# soundmeter.net
KiCad netlist of a schematic drawn in EAGLE
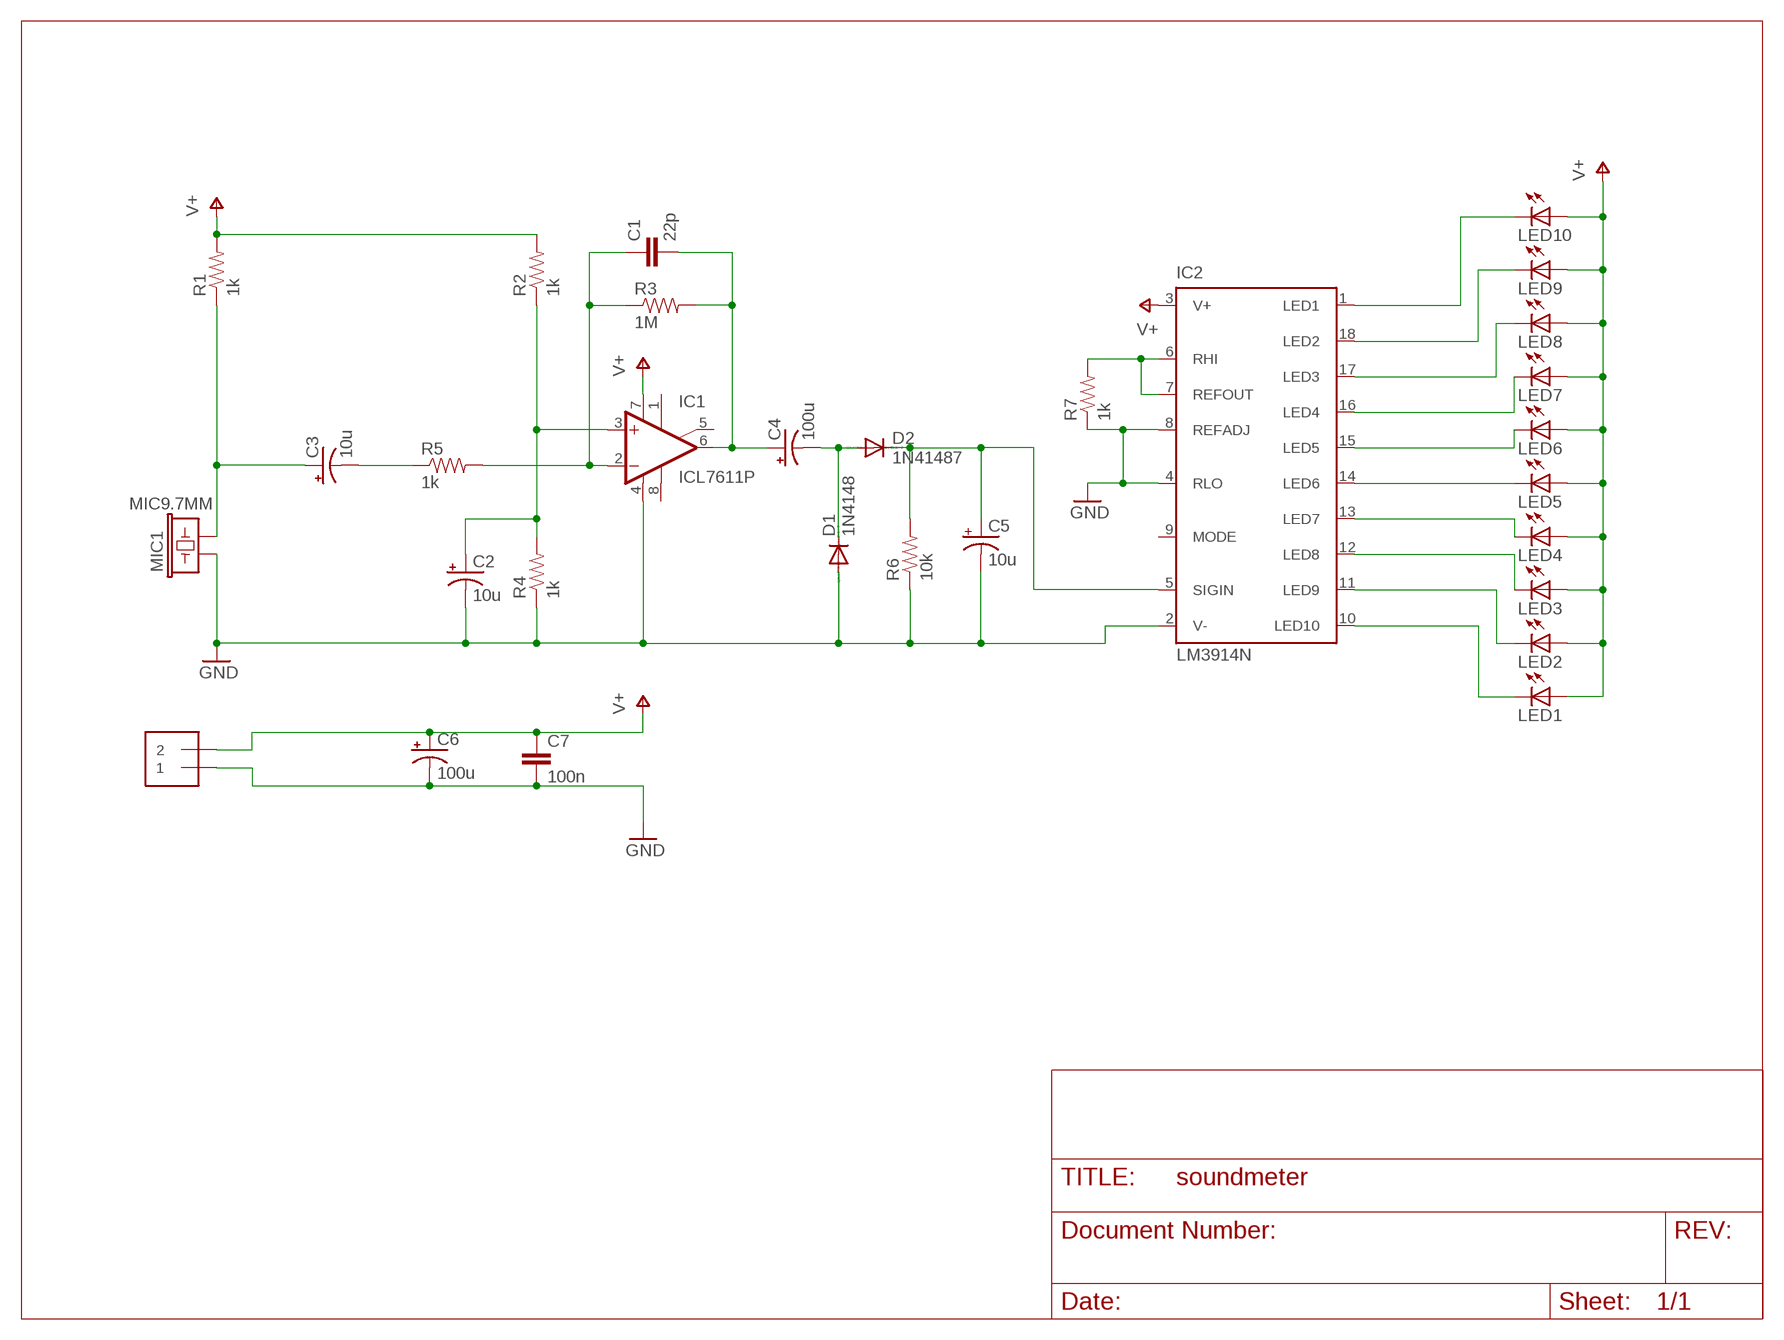
[diagram p0: schematic, sheet 1]

(export (version "E")
  (design (tool "Eeschema 10.0.6"))
  (components
    (comp (ref "C1")
      (value "22p")
      (footprint "eagle-import:CAP-PTH-SMALL")
      (libsource (lib "eagle-import") (part "CAPPTH"))
    )
    (comp (ref "C2")
      (value "10u")
      (footprint "eagle-import:CPOL-RADIAL-10UF-25V")
      (libsource (lib "eagle-import") (part "CAP_POLPTH2"))
    )
    (comp (ref "C3")
      (value "10u")
      (footprint "eagle-import:CPOL-RADIAL-10UF-25V")
      (libsource (lib "eagle-import") (part "CAP_POLPTH2"))
    )
    (comp (ref "C4")
      (value "100u")
      (footprint "eagle-import:CPOL-RADIAL-10UF-25V")
      (libsource (lib "eagle-import") (part "CAP_POLPTH2"))
    )
    (comp (ref "C5")
      (value "10u")
      (footprint "eagle-import:CPOL-RADIAL-10UF-25V")
      (libsource (lib "eagle-import") (part "CAP_POLPTH2"))
    )
    (comp (ref "C6")
      (value "100u")
      (footprint "eagle-import:CPOL-RADIAL-10UF-25V")
      (libsource (lib "eagle-import") (part "CAP_POLPTH2"))
    )
    (comp (ref "C7")
      (value "100n")
      (footprint "eagle-import:CAP-PTH-SMALL")
      (libsource (lib "eagle-import") (part "CAPPTH"))
    )
    (comp (ref "D1")
      (value "1N4148")
      (footprint "eagle-import:DO35-7")
      (libsource (lib "eagle-import") (part "1N4148DO35-7"))
    )
    (comp (ref "D2")
      (value "1N41487")
      (footprint "eagle-import:DO35-7")
      (libsource (lib "eagle-import") (part "1N4148DO35-7"))
    )
    (comp (ref "IC1")
      (value "ICL7611P")
      (footprint "eagle-import:DIL08")
      (libsource (lib "eagle-import") (part "ICL7611P"))
    )
    (comp (ref "IC2")
      (value "LM3914N")
      (footprint "eagle-import:DIL18")
      (libsource (lib "eagle-import") (part "LM391N4"))
    )
    (comp (ref "J1")
      (value "1X2-3.5MM")
      (footprint "eagle-import:1X2-3.5MM")
      (libsource (lib "eagle-import") (part "1X2-3.5MM"))
    )
    (comp (ref "LED1")
      (value "LED3MM")
      (footprint "eagle-import:LED3MM")
      (libsource (lib "eagle-import") (part "LED3MM"))
    )
    (comp (ref "LED2")
      (value "LED3MM")
      (footprint "eagle-import:LED3MM")
      (libsource (lib "eagle-import") (part "LED3MM"))
    )
    (comp (ref "LED3")
      (value "LED3MM")
      (footprint "eagle-import:LED3MM")
      (libsource (lib "eagle-import") (part "LED3MM"))
    )
    (comp (ref "LED4")
      (value "LED3MM")
      (footprint "eagle-import:LED3MM")
      (libsource (lib "eagle-import") (part "LED3MM"))
    )
    (comp (ref "LED5")
      (value "LED3MM")
      (footprint "eagle-import:LED3MM")
      (libsource (lib "eagle-import") (part "LED3MM"))
    )
    (comp (ref "LED6")
      (value "LED3MM")
      (footprint "eagle-import:LED3MM")
      (libsource (lib "eagle-import") (part "LED3MM"))
    )
    (comp (ref "LED7")
      (value "LED3MM")
      (footprint "eagle-import:LED3MM")
      (libsource (lib "eagle-import") (part "LED3MM"))
    )
    (comp (ref "LED8")
      (value "LED3MM")
      (footprint "eagle-import:LED3MM")
      (libsource (lib "eagle-import") (part "LED3MM"))
    )
    (comp (ref "LED9")
      (value "LED3MM")
      (footprint "eagle-import:LED3MM")
      (libsource (lib "eagle-import") (part "LED3MM"))
    )
    (comp (ref "LED10")
      (value "LED3MM")
      (footprint "eagle-import:LED3MM")
      (libsource (lib "eagle-import") (part "LED3MM"))
    )
    (comp (ref "MIC1")
      (value "MIC9.7MM")
      (footprint "eagle-import:MIC-9.7MM")
      (libsource (lib "eagle-import") (part "MIC9.7MM"))
    )
    (comp (ref "R1")
      (value "1k")
      (footprint "eagle-import:AXIAL-0.4")
      (libsource (lib "eagle-import") (part "RESISTORPTH-1/4W"))
    )
    (comp (ref "R2")
      (value "1k")
      (footprint "eagle-import:AXIAL-0.4")
      (libsource (lib "eagle-import") (part "RESISTORPTH-1/4W"))
    )
    (comp (ref "R3")
      (value "1M")
      (footprint "eagle-import:AXIAL-0.4")
      (libsource (lib "eagle-import") (part "RESISTORPTH-1/4W"))
    )
    (comp (ref "R4")
      (value "1k")
      (footprint "eagle-import:AXIAL-0.4")
      (libsource (lib "eagle-import") (part "RESISTORPTH-1/4W"))
    )
    (comp (ref "R5")
      (value "1k")
      (footprint "eagle-import:AXIAL-0.4")
      (libsource (lib "eagle-import") (part "RESISTORPTH-1/4W"))
    )
    (comp (ref "R6")
      (value "10k")
      (footprint "eagle-import:AXIAL-0.4")
      (libsource (lib "eagle-import") (part "RESISTORPTH-1/4W"))
    )
    (comp (ref "R7")
      (value "1k")
      (footprint "eagle-import:AXIAL-0.4")
      (libsource (lib "eagle-import") (part "RESISTORPTH-1/4W"))
    )
  )
  (nets
    (net (code "1") (name "GND") (class "Default")
      (node (ref "C2") (pin "2") (pinfunction "-_2") (pintype "passive"))
      (node (ref "C5") (pin "2") (pinfunction "-_2") (pintype "passive"))
      (node (ref "C6") (pin "2") (pinfunction "-_2") (pintype "passive"))
      (node (ref "C7") (pin "2") (pinfunction "2_2") (pintype "passive"))
      (node (ref "D1") (pin "A") (pinfunction "A_A") (pintype "passive"))
      (node (ref "IC1") (pin "4") (pinfunction "V-_4") (pintype "power_in"))
      (node (ref "IC2") (pin "2") (pinfunction "V-_2") (pintype "power_in"))
      (node (ref "IC2") (pin "4") (pinfunction "RLO_4") (pintype "input"))
      (node (ref "IC2") (pin "8") (pinfunction "REFADJ_8") (pintype "passive"))
      (node (ref "J1") (pin "1") (pinfunction "1_1") (pintype "passive"))
      (node (ref "MIC1") (pin "1") (pinfunction "1_1") (pintype "passive"))
      (node (ref "R4") (pin "P$1") (pinfunction "1_P$1") (pintype "passive"))
      (node (ref "R6") (pin "P$1") (pinfunction "1_P$1") (pintype "passive"))
      (node (ref "R7") (pin "P$1") (pinfunction "1_P$1") (pintype "passive"))
    )
    (net (code "2") (name "Net-(C2-+)") (class "Default")
      (node (ref "C2") (pin "1") (pinfunction "+_1") (pintype "passive"))
      (node (ref "IC1") (pin "3") (pinfunction "+IN_3") (pintype "input"))
      (node (ref "R2") (pin "P$1") (pinfunction "1_P$1") (pintype "passive"))
      (node (ref "R4") (pin "P$2") (pinfunction "2_P$2") (pintype "passive"))
    )
    (net (code "3") (name "Net-(C3-+)") (class "Default")
      (node (ref "C3") (pin "1") (pinfunction "+_1") (pintype "passive"))
      (node (ref "MIC1") (pin "2") (pinfunction "2_2") (pintype "passive"))
      (node (ref "R1") (pin "P$1") (pinfunction "1_P$1") (pintype "passive"))
    )
    (net (code "4") (name "Net-(C3--)") (class "Default")
      (node (ref "C3") (pin "2") (pinfunction "-_2") (pintype "passive"))
      (node (ref "R5") (pin "P$1") (pinfunction "1_P$1") (pintype "passive"))
    )
    (net (code "5") (name "Net-(C4-+)") (class "Default")
      (node (ref "C1") (pin "2") (pinfunction "2_2") (pintype "passive"))
      (node (ref "C4") (pin "1") (pinfunction "+_1") (pintype "passive"))
      (node (ref "IC1") (pin "6") (pinfunction "OUT_6") (pintype "output"))
      (node (ref "R3") (pin "P$2") (pinfunction "2_P$2") (pintype "passive"))
    )
    (net (code "6") (name "Net-(C4--)") (class "Default")
      (node (ref "C4") (pin "2") (pinfunction "-_2") (pintype "passive"))
      (node (ref "D1") (pin "C") (pinfunction "C_C") (pintype "passive"))
      (node (ref "D2") (pin "A") (pinfunction "A_A") (pintype "passive"))
    )
    (net (code "7") (name "Net-(C5-+)") (class "Default")
      (node (ref "C5") (pin "1") (pinfunction "+_1") (pintype "passive"))
      (node (ref "D2") (pin "C") (pinfunction "C_C") (pintype "passive"))
      (node (ref "IC2") (pin "5") (pinfunction "SIGIN_5") (pintype "input"))
      (node (ref "R6") (pin "P$2") (pinfunction "2_P$2") (pintype "passive"))
    )
    (net (code "8") (name "Net-(IC1--IN)") (class "Default")
      (node (ref "C1") (pin "1") (pinfunction "1_1") (pintype "passive"))
      (node (ref "IC1") (pin "2") (pinfunction "-IN_2") (pintype "input"))
      (node (ref "R3") (pin "P$1") (pinfunction "1_P$1") (pintype "passive"))
      (node (ref "R5") (pin "P$2") (pinfunction "2_P$2") (pintype "passive"))
    )
    (net (code "9") (name "Net-(IC2-LED1)") (class "Default")
      (node (ref "IC2") (pin "1") (pinfunction "LED1_1") (pintype "output"))
      (node (ref "LED10") (pin "K") (pinfunction "C_K") (pintype "passive"))
    )
    (net (code "10") (name "Net-(IC2-LED2)") (class "Default")
      (node (ref "IC2") (pin "18") (pinfunction "LED2_18") (pintype "output"))
      (node (ref "LED9") (pin "K") (pinfunction "C_K") (pintype "passive"))
    )
    (net (code "11") (name "Net-(IC2-LED3)") (class "Default")
      (node (ref "IC2") (pin "17") (pinfunction "LED3_17") (pintype "output"))
      (node (ref "LED8") (pin "K") (pinfunction "C_K") (pintype "passive"))
    )
    (net (code "12") (name "Net-(IC2-LED4)") (class "Default")
      (node (ref "IC2") (pin "16") (pinfunction "LED4_16") (pintype "output"))
      (node (ref "LED7") (pin "K") (pinfunction "C_K") (pintype "passive"))
    )
    (net (code "13") (name "Net-(IC2-LED5)") (class "Default")
      (node (ref "IC2") (pin "15") (pinfunction "LED5_15") (pintype "output"))
      (node (ref "LED6") (pin "K") (pinfunction "C_K") (pintype "passive"))
    )
    (net (code "14") (name "Net-(IC2-LED6)") (class "Default")
      (node (ref "IC2") (pin "14") (pinfunction "LED6_14") (pintype "output"))
      (node (ref "LED5") (pin "K") (pinfunction "C_K") (pintype "passive"))
    )
    (net (code "15") (name "Net-(IC2-LED7)") (class "Default")
      (node (ref "IC2") (pin "13") (pinfunction "LED7_13") (pintype "output"))
      (node (ref "LED4") (pin "K") (pinfunction "C_K") (pintype "passive"))
    )
    (net (code "16") (name "Net-(IC2-LED8)") (class "Default")
      (node (ref "IC2") (pin "12") (pinfunction "LED8_12") (pintype "output"))
      (node (ref "LED3") (pin "K") (pinfunction "C_K") (pintype "passive"))
    )
    (net (code "17") (name "Net-(IC2-LED9)") (class "Default")
      (node (ref "IC2") (pin "11") (pinfunction "LED9_11") (pintype "output"))
      (node (ref "LED2") (pin "K") (pinfunction "C_K") (pintype "passive"))
    )
    (net (code "18") (name "Net-(IC2-LED10)") (class "Default")
      (node (ref "IC2") (pin "10") (pinfunction "LED10_10") (pintype "output"))
      (node (ref "LED1") (pin "K") (pinfunction "C_K") (pintype "passive"))
    )
    (net (code "19") (name "Net-(IC2-REFOUT)") (class "Default")
      (node (ref "IC2") (pin "6") (pinfunction "RHI_6") (pintype "input"))
      (node (ref "IC2") (pin "7") (pinfunction "REFOUT_7") (pintype "output"))
      (node (ref "R7") (pin "P$2") (pinfunction "2_P$2") (pintype "passive"))
    )
    (net (code "20") (name "V+") (class "Default")
      (node (ref "C6") (pin "1") (pinfunction "+_1") (pintype "passive"))
      (node (ref "C7") (pin "1") (pinfunction "1_1") (pintype "passive"))
      (node (ref "IC1") (pin "7") (pinfunction "V+_7") (pintype "power_in"))
      (node (ref "IC2") (pin "3") (pinfunction "V+_3") (pintype "power_in"))
      (node (ref "J1") (pin "2") (pinfunction "2_2") (pintype "passive"))
      (node (ref "LED1") (pin "A") (pinfunction "A_A") (pintype "passive"))
      (node (ref "LED10") (pin "A") (pinfunction "A_A") (pintype "passive"))
      (node (ref "LED2") (pin "A") (pinfunction "A_A") (pintype "passive"))
      (node (ref "LED3") (pin "A") (pinfunction "A_A") (pintype "passive"))
      (node (ref "LED4") (pin "A") (pinfunction "A_A") (pintype "passive"))
      (node (ref "LED5") (pin "A") (pinfunction "A_A") (pintype "passive"))
      (node (ref "LED6") (pin "A") (pinfunction "A_A") (pintype "passive"))
      (node (ref "LED7") (pin "A") (pinfunction "A_A") (pintype "passive"))
      (node (ref "LED8") (pin "A") (pinfunction "A_A") (pintype "passive"))
      (node (ref "LED9") (pin "A") (pinfunction "A_A") (pintype "passive"))
      (node (ref "R1") (pin "P$2") (pinfunction "2_P$2") (pintype "passive"))
      (node (ref "R2") (pin "P$2") (pinfunction "2_P$2") (pintype "passive"))
    )
    (net (code "21") (name "unconnected-(IC1-ON1-Pad1)") (class "Default")
      (node (ref "IC1") (pin "1") (pinfunction "ON1_1") (pintype "passive"))
    )
    (net (code "22") (name "unconnected-(IC1-ON2-Pad5)") (class "Default")
      (node (ref "IC1") (pin "5") (pinfunction "ON2_5") (pintype "passive"))
    )
    (net (code "23") (name "unconnected-(IC1-OPT-Pad8)") (class "Default")
      (node (ref "IC1") (pin "8") (pinfunction "OPT_8") (pintype "passive"))
    )
    (net (code "24") (name "unconnected-(IC2-MODE-Pad9)") (class "Default")
      (node (ref "IC2") (pin "9") (pinfunction "MODE_9") (pintype "input"))
    )
  )
)
